# Sheet1.net
KiCad netlist of a schematic drawn in Altium Designer
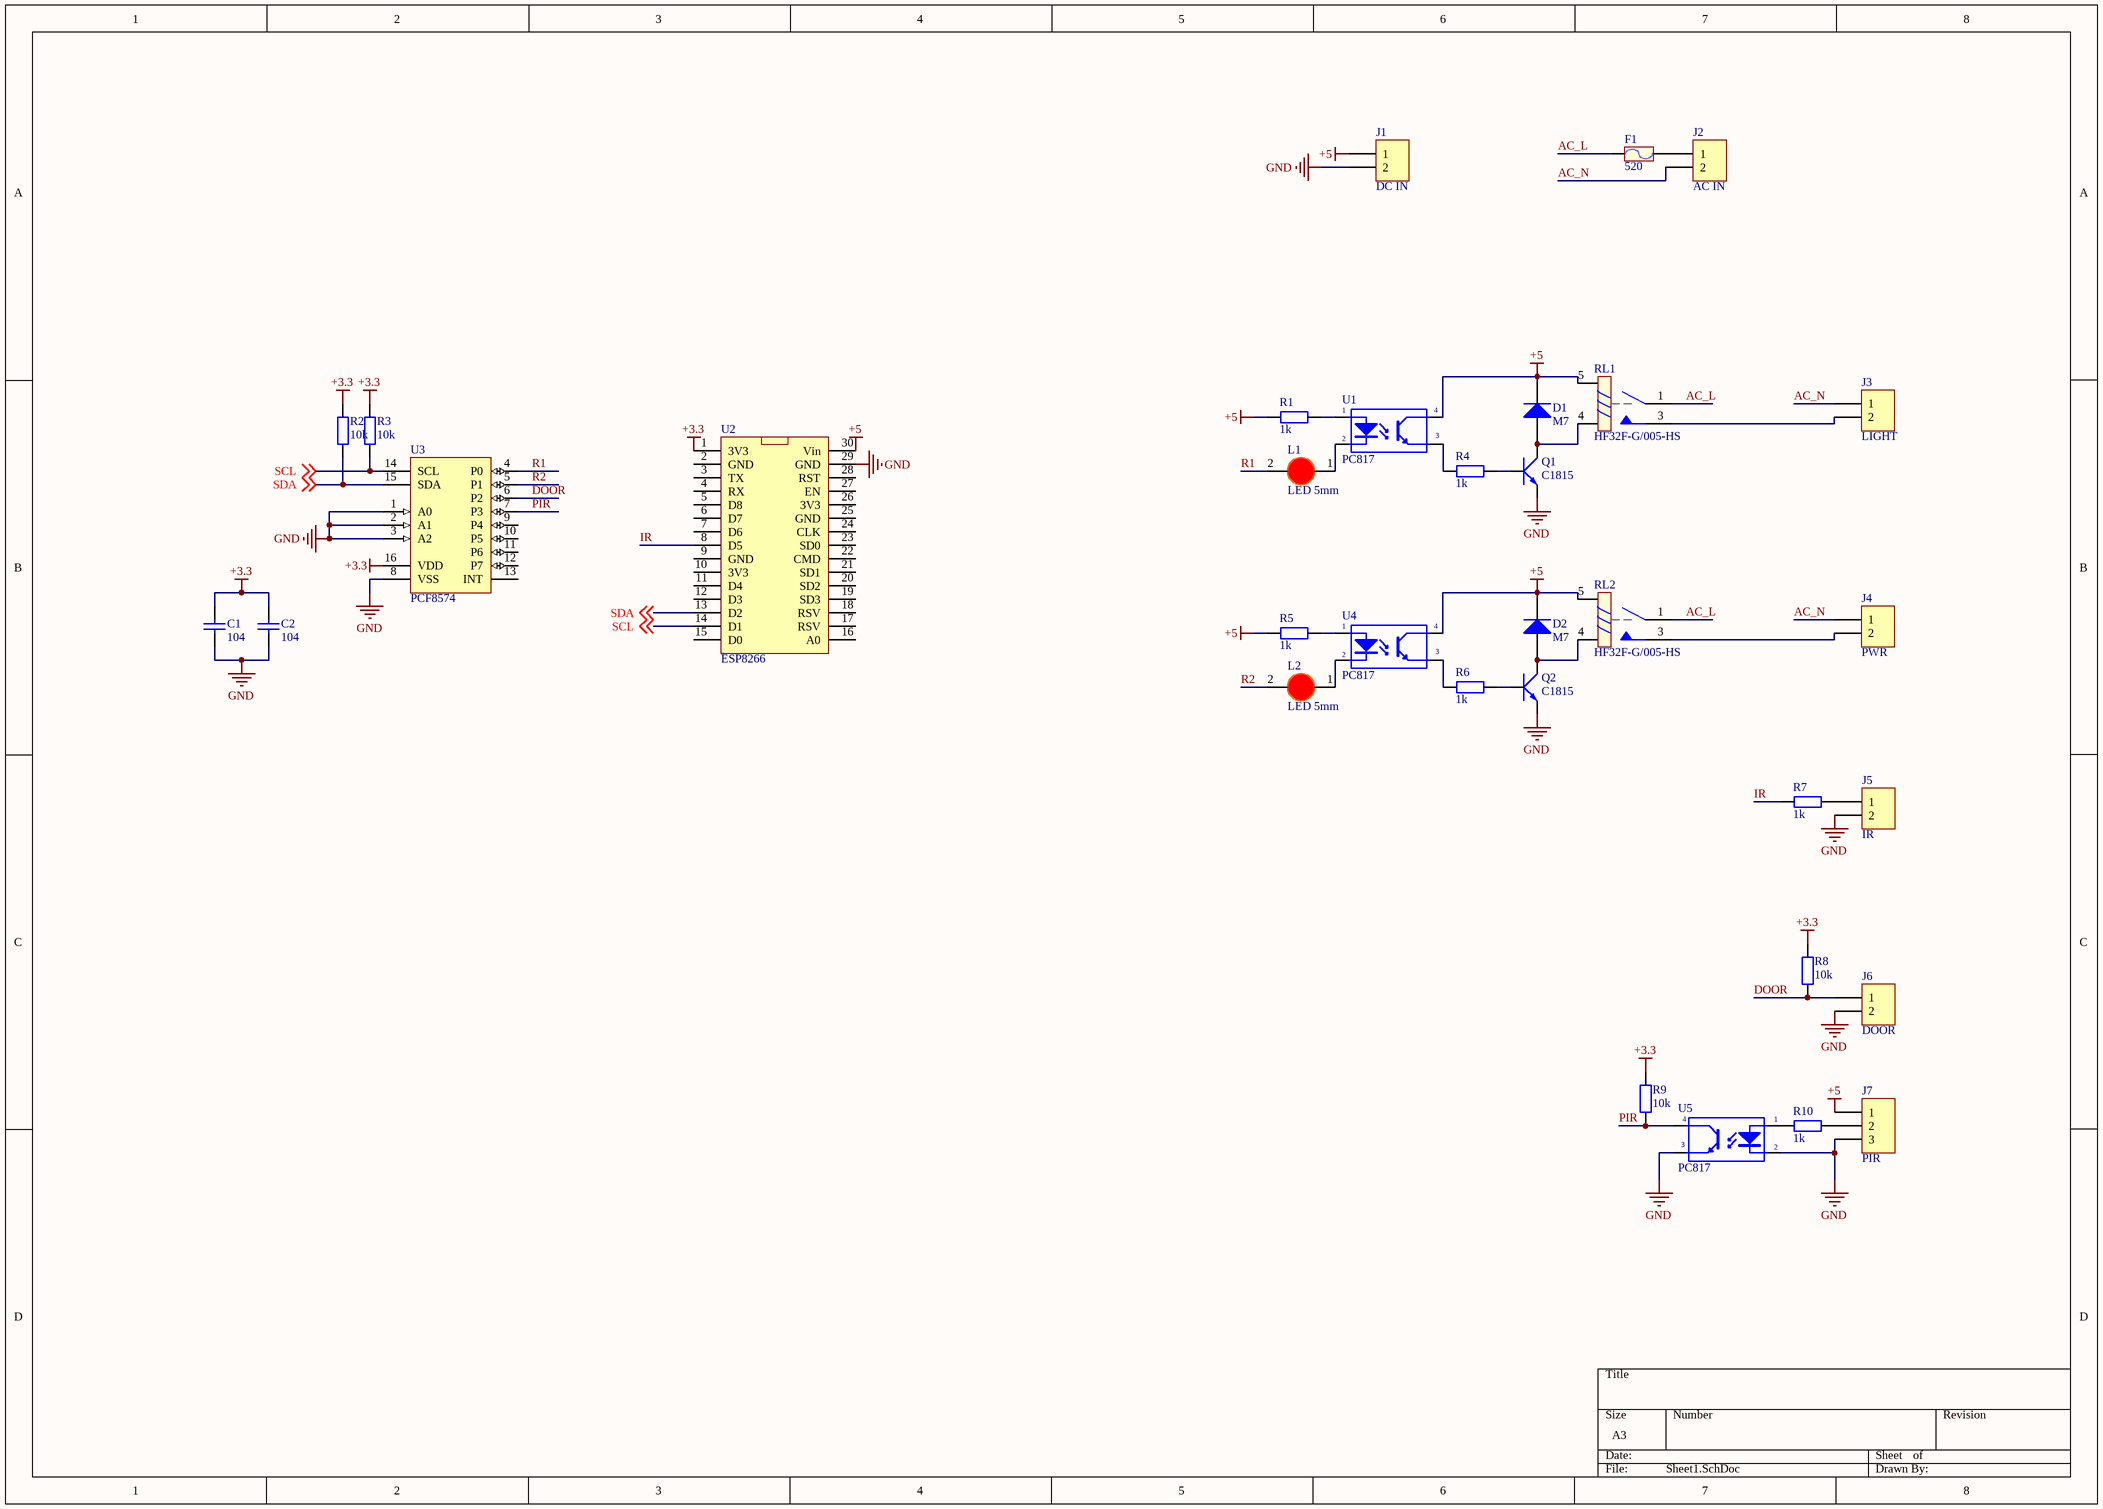
[diagram p0: Sheet1.SchDoc]

(export (version "E")
  (design (tool "Eeschema 10.0.6"))
  (components
    (comp (ref "C1")
      (value "104")
      (footprint "tu 0805")
      (description "Dán")
      (libsource (lib "Altium_Lib_by_KhueNguyenCreator") (part "Tu 0805 104 50V 10%"))
    )
    (comp (ref "C2")
      (value "104")
      (footprint "tu 0805")
      (description "Dán")
      (libsource (lib "Altium_Lib_by_KhueNguyenCreator") (part "Tu 0805 104 50V 10%"))
    )
    (comp (ref "D1")
      (value "M7")
      (footprint "DIODE SMA")
      (description "Dán")
      (libsource (lib "Altium_Lib_by_KhueNguyenCreator") (part "Diode M7 ( 4007 )"))
    )
    (comp (ref "D2")
      (value "M7")
      (footprint "DIODE SMA")
      (description "Dán")
      (libsource (lib "Altium_Lib_by_KhueNguyenCreator") (part "Diode M7 ( 4007 )"))
    )
    (comp (ref "F1")
      (value "520")
      (footprint "De Cau Chi 520 630")
      (description "5x20mm")
      (libsource (lib "Altium_Lib_by_KhueNguyenCreator") (part "De Cau Chi 520 630"))
    )
    (comp (ref "J1")
      (value "DC IN")
      (footprint "CON 2 HT3.96")
      (description "CON2 KF terminal")
      (libsource (lib "iuh-thuc-hanh") (part "CON 2 EDG5.08"))
    )
    (comp (ref "J2")
      (value "AC IN")
      (footprint "CON 2 2EDG5.08 B")
      (description "CON2 KF terminal")
      (libsource (lib "iuh-thuc-hanh") (part "CON 2 EDG5.08"))
    )
    (comp (ref "J3")
      (value "LIGHT")
      (footprint "CON 2 2EDG5.08 B")
      (description "CON2 KF terminal")
      (libsource (lib "iuh-thuc-hanh") (part "CON 2 EDG5.08"))
    )
    (comp (ref "J4")
      (value "PWR")
      (footprint "CON 2 2EDG5.08 B")
      (description "CON2 KF terminal")
      (libsource (lib "iuh-thuc-hanh") (part "CON 2 EDG5.08"))
    )
    (comp (ref "J5")
      (value "IR")
      (footprint "CON 2 HT3.96")
      (description "CON2 KF terminal")
      (libsource (lib "iuh-thuc-hanh") (part "CON 2 EDG5.08"))
    )
    (comp (ref "J6")
      (value "DOOR")
      (footprint "CON 2 HT3.96")
      (description "CON2 KF terminal")
      (libsource (lib "iuh-thuc-hanh") (part "CON 2 EDG5.08"))
    )
    (comp (ref "J7")
      (value "PIR")
      (footprint "KF3-3.96")
      (description "CON3 KF terminal")
      (libsource (lib "iuh-thuc-hanh") (part "CON 3 EDG"))
    )
    (comp (ref "L1")
      (value "LED 5mm")
      (footprint "LED-5MM-RED")
      (description "Cắm")
      (libsource (lib "Altium_Lib_by_KhueNguyenCreator") (part "LED 5mm Do"))
    )
    (comp (ref "L2")
      (value "LED 5mm")
      (footprint "LED-5MM-RED")
      (description "Cắm")
      (libsource (lib "Altium_Lib_by_KhueNguyenCreator") (part "LED 5mm Do"))
    )
    (comp (ref "Q1")
      (value "C1815")
      (footprint "TO92")
      (description "NPN transistor")
      (libsource (lib "Altium_Lib_by_KhueNguyenCreator") (part "Trans C1815 DIP"))
    )
    (comp (ref "Q2")
      (value "C1815")
      (footprint "TO92")
      (description "NPN transistor")
      (libsource (lib "Altium_Lib_by_KhueNguyenCreator") (part "Trans C1815 DIP"))
    )
    (comp (ref "R1")
      (value "1k")
      (footprint "tro smd 0805")
      (description "Dán")
      (libsource (lib "Altium_Lib_by_KhueNguyenCreator") (part "Tro 0805 1% 1k"))
    )
    (comp (ref "R2")
      (value "10k")
      (footprint "tro smd 0805")
      (description "Dán")
      (libsource (lib "Altium_Lib_by_KhueNguyenCreator") (part "Tro 0805 1% 10k"))
    )
    (comp (ref "R3")
      (value "10k")
      (footprint "tro smd 0805")
      (description "Dán")
      (libsource (lib "Altium_Lib_by_KhueNguyenCreator") (part "Tro 0805 1% 10k"))
    )
    (comp (ref "R4")
      (value "1k")
      (footprint "tro smd 0805")
      (description "Dán")
      (libsource (lib "Altium_Lib_by_KhueNguyenCreator") (part "Tro 0805 1% 1k"))
    )
    (comp (ref "R5")
      (value "1k")
      (footprint "tro smd 0805")
      (description "Dán")
      (libsource (lib "Altium_Lib_by_KhueNguyenCreator") (part "Tro 0805 1% 1k"))
    )
    (comp (ref "R6")
      (value "1k")
      (footprint "tro smd 0805")
      (description "Dán")
      (libsource (lib "Altium_Lib_by_KhueNguyenCreator") (part "Tro 0805 1% 1k"))
    )
    (comp (ref "R7")
      (value "1k")
      (footprint "tro smd 0805")
      (description "Dán")
      (libsource (lib "Altium_Lib_by_KhueNguyenCreator") (part "Tro 0805 1% 1k"))
    )
    (comp (ref "R8")
      (value "10k")
      (footprint "tro smd 0805")
      (description "Dán")
      (libsource (lib "Altium_Lib_by_KhueNguyenCreator") (part "Tro 0805 1% 10k"))
    )
    (comp (ref "R9")
      (value "10k")
      (footprint "tro smd 0805")
      (description "Dán")
      (libsource (lib "Altium_Lib_by_KhueNguyenCreator") (part "Tro 0805 1% 10k"))
    )
    (comp (ref "R10")
      (value "1k")
      (footprint "tro smd 0805")
      (description "Dán")
      (libsource (lib "Altium_Lib_by_KhueNguyenCreator") (part "Tro 0805 1% 1k"))
    )
    (comp (ref "RL1")
      (value "HF32F-G/005-HS")
      (footprint "HF32F-G")
      (description "Relay hongfa 10A 4P HF32F-G/005-HS")
      (libsource (lib "iuh-thuc-hanh") (part "Relay HF 10A"))
    )
    (comp (ref "RL2")
      (value "HF32F-G/005-HS")
      (footprint "HF32F-G")
      (description "Relay hongfa 10A 4P HF32F-G/005-HS")
      (libsource (lib "iuh-thuc-hanh") (part "Relay HF 10A"))
    )
    (comp (ref "U1")
      (value "PC817")
      (footprint "DIP4")
      (description "Single Opto")
      (libsource (lib "LIBRARY1") (part "PC817"))
    )
    (comp (ref "U2")
      (value "ESP8266")
      (footprint "NODE MCU CH340")
      (description "ESP8266 nodemcu 1.0")
      (libsource (lib "iuh-thuc-hanh") (part "NODEMCU 1.0"))
    )
    (comp (ref "U3") (value "PCF8574") (footprint "DIP16") (libsource (lib "iuh-thuc-hanh") (part "PCF8574")))
    (comp (ref "U4")
      (value "PC817")
      (footprint "DIP4")
      (description "Single Opto")
      (libsource (lib "LIBRARY1") (part "PC817"))
    )
    (comp (ref "U5")
      (value "PC817")
      (footprint "DIP4")
      (description "Single Opto")
      (libsource (lib "LIBRARY1") (part "PC817"))
    )
  )
  (nets
    (net (code "1") (name "+3.3") (class "Default")
      (node (ref "C1") (pin "1") (pinfunction "1_1") (pintype "passive"))
      (node (ref "C2") (pin "1") (pinfunction "1_1") (pintype "passive"))
      (node (ref "R2") (pin "2") (pinfunction "2_2") (pintype "passive"))
      (node (ref "R3") (pin "2") (pinfunction "2_2") (pintype "passive"))
      (node (ref "R8") (pin "2") (pinfunction "2_2") (pintype "passive"))
      (node (ref "R9") (pin "2") (pinfunction "2_2") (pintype "passive"))
      (node (ref "U2") (pin "1") (pinfunction "3V3_1") (pintype "passive"))
      (node (ref "U3") (pin "16") (pinfunction "VDD_16") (pintype "passive"))
    )
    (net (code "2") (name "+5") (class "Default")
      (node (ref "D1") (pin "2") (pinfunction "K_2") (pintype "passive"))
      (node (ref "D2") (pin "2") (pinfunction "K_2") (pintype "passive"))
      (node (ref "J1") (pin "1") (pinfunction "1_1") (pintype "passive"))
      (node (ref "J7") (pin "1") (pinfunction "1_1") (pintype "passive"))
      (node (ref "R1") (pin "1") (pinfunction "1_1") (pintype "passive"))
      (node (ref "R5") (pin "1") (pinfunction "1_1") (pintype "passive"))
      (node (ref "RL1") (pin "5") (pinfunction "5_5") (pintype "passive"))
      (node (ref "RL2") (pin "5") (pinfunction "5_5") (pintype "passive"))
      (node (ref "U1") (pin "4") (pinfunction "C_4") (pintype "passive"))
      (node (ref "U2") (pin "30") (pinfunction "Vin_30") (pintype "passive"))
      (node (ref "U4") (pin "4") (pinfunction "C_4") (pintype "passive"))
    )
    (net (code "3") (name "/AC_L") (class "Default")
      (node (ref "F1") (pin "1") (pinfunction "1_1") (pintype "passive"))
      (node (ref "RL1") (pin "1") (pinfunction "1_1") (pintype "passive"))
      (node (ref "RL2") (pin "1") (pinfunction "1_1") (pintype "passive"))
    )
    (net (code "4") (name "/AC_N") (class "Default")
      (node (ref "J2") (pin "2") (pinfunction "2_2") (pintype "passive"))
      (node (ref "J3") (pin "1") (pinfunction "1_1") (pintype "passive"))
      (node (ref "J4") (pin "1") (pinfunction "1_1") (pintype "passive"))
    )
    (net (code "5") (name "/DOOR") (class "Default")
      (node (ref "J6") (pin "1") (pinfunction "1_1") (pintype "passive"))
      (node (ref "R8") (pin "1") (pinfunction "1_1") (pintype "passive"))
      (node (ref "U3") (pin "6") (pinfunction "P2_6") (pintype "bidirectional"))
    )
    (net (code "6") (name "/IR") (class "Default")
      (node (ref "R7") (pin "1") (pinfunction "1_1") (pintype "passive"))
      (node (ref "U2") (pin "8") (pinfunction "D5_8") (pintype "passive"))
    )
    (net (code "7") (name "/PIR") (class "Default")
      (node (ref "R9") (pin "1") (pinfunction "1_1") (pintype "passive"))
      (node (ref "U3") (pin "7") (pinfunction "P3_7") (pintype "bidirectional"))
      (node (ref "U5") (pin "4") (pinfunction "C_4") (pintype "passive"))
    )
    (net (code "8") (name "/R1") (class "Default")
      (node (ref "L1") (pin "2") (pinfunction "K_2") (pintype "passive"))
      (node (ref "U3") (pin "4") (pinfunction "P0_4") (pintype "bidirectional"))
    )
    (net (code "9") (name "/R2") (class "Default")
      (node (ref "L2") (pin "2") (pinfunction "K_2") (pintype "passive"))
      (node (ref "U3") (pin "5") (pinfunction "P1_5") (pintype "bidirectional"))
    )
    (net (code "10") (name "GND") (class "Default")
      (node (ref "C1") (pin "2") (pinfunction "2_2") (pintype "passive"))
      (node (ref "C2") (pin "2") (pinfunction "2_2") (pintype "passive"))
      (node (ref "J1") (pin "2") (pinfunction "2_2") (pintype "passive"))
      (node (ref "J5") (pin "2") (pinfunction "2_2") (pintype "passive"))
      (node (ref "J6") (pin "2") (pinfunction "2_2") (pintype "passive"))
      (node (ref "J7") (pin "3") (pinfunction "3_3") (pintype "passive"))
      (node (ref "Q1") (pin "1") (pinfunction "E_1") (pintype "passive"))
      (node (ref "Q2") (pin "1") (pinfunction "E_1") (pintype "passive"))
      (node (ref "U2") (pin "29") (pinfunction "GND_29") (pintype "passive"))
      (node (ref "U3") (pin "1") (pinfunction "A0_1") (pintype "input"))
      (node (ref "U3") (pin "2") (pinfunction "A1_2") (pintype "input"))
      (node (ref "U3") (pin "3") (pinfunction "A2_3") (pintype "input"))
      (node (ref "U3") (pin "8") (pinfunction "VSS_8") (pintype "passive"))
      (node (ref "U5") (pin "2") (pinfunction "K_2") (pintype "passive"))
      (node (ref "U5") (pin "3") (pinfunction "E_3") (pintype "passive"))
    )
    (net (code "11") (name "Net-(D1-A)") (class "Default")
      (node (ref "D1") (pin "1") (pinfunction "A_1") (pintype "passive"))
      (node (ref "Q1") (pin "2") (pinfunction "C_2") (pintype "passive"))
      (node (ref "RL1") (pin "4") (pinfunction "4_4") (pintype "passive"))
    )
    (net (code "12") (name "Net-(D2-A)") (class "Default")
      (node (ref "D2") (pin "1") (pinfunction "A_1") (pintype "passive"))
      (node (ref "Q2") (pin "2") (pinfunction "C_2") (pintype "passive"))
      (node (ref "RL2") (pin "4") (pinfunction "4_4") (pintype "passive"))
    )
    (net (code "13") (name "Net-(F1-Pad2)") (class "Default")
      (node (ref "F1") (pin "2") (pinfunction "2_2") (pintype "passive"))
      (node (ref "J2") (pin "1") (pinfunction "1_1") (pintype "passive"))
    )
    (net (code "14") (name "Net-(J3-Pad2)") (class "Default")
      (node (ref "J3") (pin "2") (pinfunction "2_2") (pintype "passive"))
      (node (ref "RL1") (pin "3") (pinfunction "3_3") (pintype "passive"))
    )
    (net (code "15") (name "Net-(J4-Pad2)") (class "Default")
      (node (ref "J4") (pin "2") (pinfunction "2_2") (pintype "passive"))
      (node (ref "RL2") (pin "3") (pinfunction "3_3") (pintype "passive"))
    )
    (net (code "16") (name "Net-(J5-Pad1)") (class "Default")
      (node (ref "J5") (pin "1") (pinfunction "1_1") (pintype "passive"))
      (node (ref "R7") (pin "2") (pinfunction "2_2") (pintype "passive"))
    )
    (net (code "17") (name "Net-(J7-Pad2)") (class "Default")
      (node (ref "J7") (pin "2") (pinfunction "2_2") (pintype "passive"))
      (node (ref "R10") (pin "1") (pinfunction "1_1") (pintype "passive"))
    )
    (net (code "18") (name "Net-(L1-A)") (class "Default")
      (node (ref "L1") (pin "1") (pinfunction "A_1") (pintype "passive"))
      (node (ref "U1") (pin "2") (pinfunction "K_2") (pintype "passive"))
    )
    (net (code "19") (name "Net-(L2-A)") (class "Default")
      (node (ref "L2") (pin "1") (pinfunction "A_1") (pintype "passive"))
      (node (ref "U4") (pin "2") (pinfunction "K_2") (pintype "passive"))
    )
    (net (code "20") (name "Net-(Q1-B)") (class "Default")
      (node (ref "Q1") (pin "3") (pinfunction "B_3") (pintype "passive"))
      (node (ref "R4") (pin "2") (pinfunction "2_2") (pintype "passive"))
    )
    (net (code "21") (name "Net-(Q2-B)") (class "Default")
      (node (ref "Q2") (pin "3") (pinfunction "B_3") (pintype "passive"))
      (node (ref "R6") (pin "2") (pinfunction "2_2") (pintype "passive"))
    )
    (net (code "22") (name "Net-(U1-A)") (class "Default")
      (node (ref "R1") (pin "2") (pinfunction "2_2") (pintype "passive"))
      (node (ref "U1") (pin "1") (pinfunction "A_1") (pintype "passive"))
    )
    (net (code "23") (name "Net-(U1-E)") (class "Default")
      (node (ref "R4") (pin "1") (pinfunction "1_1") (pintype "passive"))
      (node (ref "U1") (pin "3") (pinfunction "E_3") (pintype "passive"))
    )
    (net (code "24") (name "Net-(U4-A)") (class "Default")
      (node (ref "R5") (pin "2") (pinfunction "2_2") (pintype "passive"))
      (node (ref "U4") (pin "1") (pinfunction "A_1") (pintype "passive"))
    )
    (net (code "25") (name "Net-(U4-E)") (class "Default")
      (node (ref "R6") (pin "1") (pinfunction "1_1") (pintype "passive"))
      (node (ref "U4") (pin "3") (pinfunction "E_3") (pintype "passive"))
    )
    (net (code "26") (name "Net-(U5-A)") (class "Default")
      (node (ref "R10") (pin "2") (pinfunction "2_2") (pintype "passive"))
      (node (ref "U5") (pin "1") (pinfunction "A_1") (pintype "passive"))
    )
    (net (code "27") (name "SCL") (class "Default")
      (node (ref "R3") (pin "1") (pinfunction "1_1") (pintype "passive"))
      (node (ref "U2") (pin "14") (pinfunction "D1_14") (pintype "passive"))
      (node (ref "U3") (pin "14") (pinfunction "SCL_14") (pintype "passive"))
    )
    (net (code "28") (name "SDA") (class "Default")
      (node (ref "R2") (pin "1") (pinfunction "1_1") (pintype "passive"))
      (node (ref "U2") (pin "13") (pinfunction "D2_13") (pintype "passive"))
      (node (ref "U3") (pin "15") (pinfunction "SDA_15") (pintype "passive"))
    )
    (net (code "29") (name "unconnected-(U2-3V3-Pad10)") (class "Default")
      (node (ref "U2") (pin "10") (pinfunction "3V3_10") (pintype "passive"))
    )
    (net (code "30") (name "unconnected-(U2-3V3-Pad26)") (class "Default")
      (node (ref "U2") (pin "26") (pinfunction "3V3_26") (pintype "passive"))
    )
    (net (code "31") (name "unconnected-(U2-A0-Pad16)") (class "Default")
      (node (ref "U2") (pin "16") (pinfunction "A0_16") (pintype "passive"))
    )
    (net (code "32") (name "unconnected-(U2-CLK-Pad24)") (class "Default")
      (node (ref "U2") (pin "24") (pinfunction "CLK_24") (pintype "passive"))
    )
    (net (code "33") (name "unconnected-(U2-CMD-Pad22)") (class "Default")
      (node (ref "U2") (pin "22") (pinfunction "CMD_22") (pintype "passive"))
    )
    (net (code "34") (name "unconnected-(U2-D0-Pad15)") (class "Default")
      (node (ref "U2") (pin "15") (pinfunction "D0_15") (pintype "passive"))
    )
    (net (code "35") (name "unconnected-(U2-D3-Pad12)") (class "Default")
      (node (ref "U2") (pin "12") (pinfunction "D3_12") (pintype "passive"))
    )
    (net (code "36") (name "unconnected-(U2-D4-Pad11)") (class "Default")
      (node (ref "U2") (pin "11") (pinfunction "D4_11") (pintype "passive"))
    )
    (net (code "37") (name "unconnected-(U2-D6-Pad7)") (class "Default")
      (node (ref "U2") (pin "7") (pinfunction "D6_7") (pintype "passive"))
    )
    (net (code "38") (name "unconnected-(U2-D7-Pad6)") (class "Default")
      (node (ref "U2") (pin "6") (pinfunction "D7_6") (pintype "passive"))
    )
    (net (code "39") (name "unconnected-(U2-D8-Pad5)") (class "Default")
      (node (ref "U2") (pin "5") (pinfunction "D8_5") (pintype "passive"))
    )
    (net (code "40") (name "unconnected-(U2-EN-Pad27)") (class "Default")
      (node (ref "U2") (pin "27") (pinfunction "EN_27") (pintype "passive"))
    )
    (net (code "41") (name "unconnected-(U2-GND-Pad2)") (class "Default")
      (node (ref "U2") (pin "2") (pinfunction "GND_2") (pintype "passive"))
    )
    (net (code "42") (name "unconnected-(U2-GND-Pad9)") (class "Default")
      (node (ref "U2") (pin "9") (pinfunction "GND_9") (pintype "passive"))
    )
    (net (code "43") (name "unconnected-(U2-GND-Pad25)") (class "Default")
      (node (ref "U2") (pin "25") (pinfunction "GND_25") (pintype "passive"))
    )
    (net (code "44") (name "unconnected-(U2-RST-Pad28)") (class "Default")
      (node (ref "U2") (pin "28") (pinfunction "RST_28") (pintype "passive"))
    )
    (net (code "45") (name "unconnected-(U2-RSV-Pad17)") (class "Default")
      (node (ref "U2") (pin "17") (pinfunction "RSV_17") (pintype "passive"))
    )
    (net (code "46") (name "unconnected-(U2-RSV-Pad18)") (class "Default")
      (node (ref "U2") (pin "18") (pinfunction "RSV_18") (pintype "passive"))
    )
    (net (code "47") (name "unconnected-(U2-RX-Pad4)") (class "Default")
      (node (ref "U2") (pin "4") (pinfunction "RX_4") (pintype "passive"))
    )
    (net (code "48") (name "unconnected-(U2-SD0-Pad23)") (class "Default")
      (node (ref "U2") (pin "23") (pinfunction "SD0_23") (pintype "passive"))
    )
    (net (code "49") (name "unconnected-(U2-SD1-Pad21)") (class "Default")
      (node (ref "U2") (pin "21") (pinfunction "SD1_21") (pintype "passive"))
    )
    (net (code "50") (name "unconnected-(U2-SD2-Pad20)") (class "Default")
      (node (ref "U2") (pin "20") (pinfunction "SD2_20") (pintype "passive"))
    )
    (net (code "51") (name "unconnected-(U2-SD3-Pad19)") (class "Default")
      (node (ref "U2") (pin "19") (pinfunction "SD3_19") (pintype "passive"))
    )
    (net (code "52") (name "unconnected-(U2-TX-Pad3)") (class "Default")
      (node (ref "U2") (pin "3") (pinfunction "TX_3") (pintype "passive"))
    )
    (net (code "53") (name "unconnected-(U3-INT-Pad13)") (class "Default")
      (node (ref "U3") (pin "13") (pinfunction "INT_13") (pintype "passive"))
    )
    (net (code "54") (name "unconnected-(U3-P4-Pad9)") (class "Default")
      (node (ref "U3") (pin "9") (pinfunction "P4_9") (pintype "bidirectional"))
    )
    (net (code "55") (name "unconnected-(U3-P5-Pad10)") (class "Default")
      (node (ref "U3") (pin "10") (pinfunction "P5_10") (pintype "bidirectional"))
    )
    (net (code "56") (name "unconnected-(U3-P6-Pad11)") (class "Default")
      (node (ref "U3") (pin "11") (pinfunction "P6_11") (pintype "bidirectional"))
    )
    (net (code "57") (name "unconnected-(U3-P7-Pad12)") (class "Default")
      (node (ref "U3") (pin "12") (pinfunction "P7_12") (pintype "bidirectional"))
    )
  )
)
